# gesture_control_robot_rx.net
KiCad netlist of a schematic drawn in EAGLE
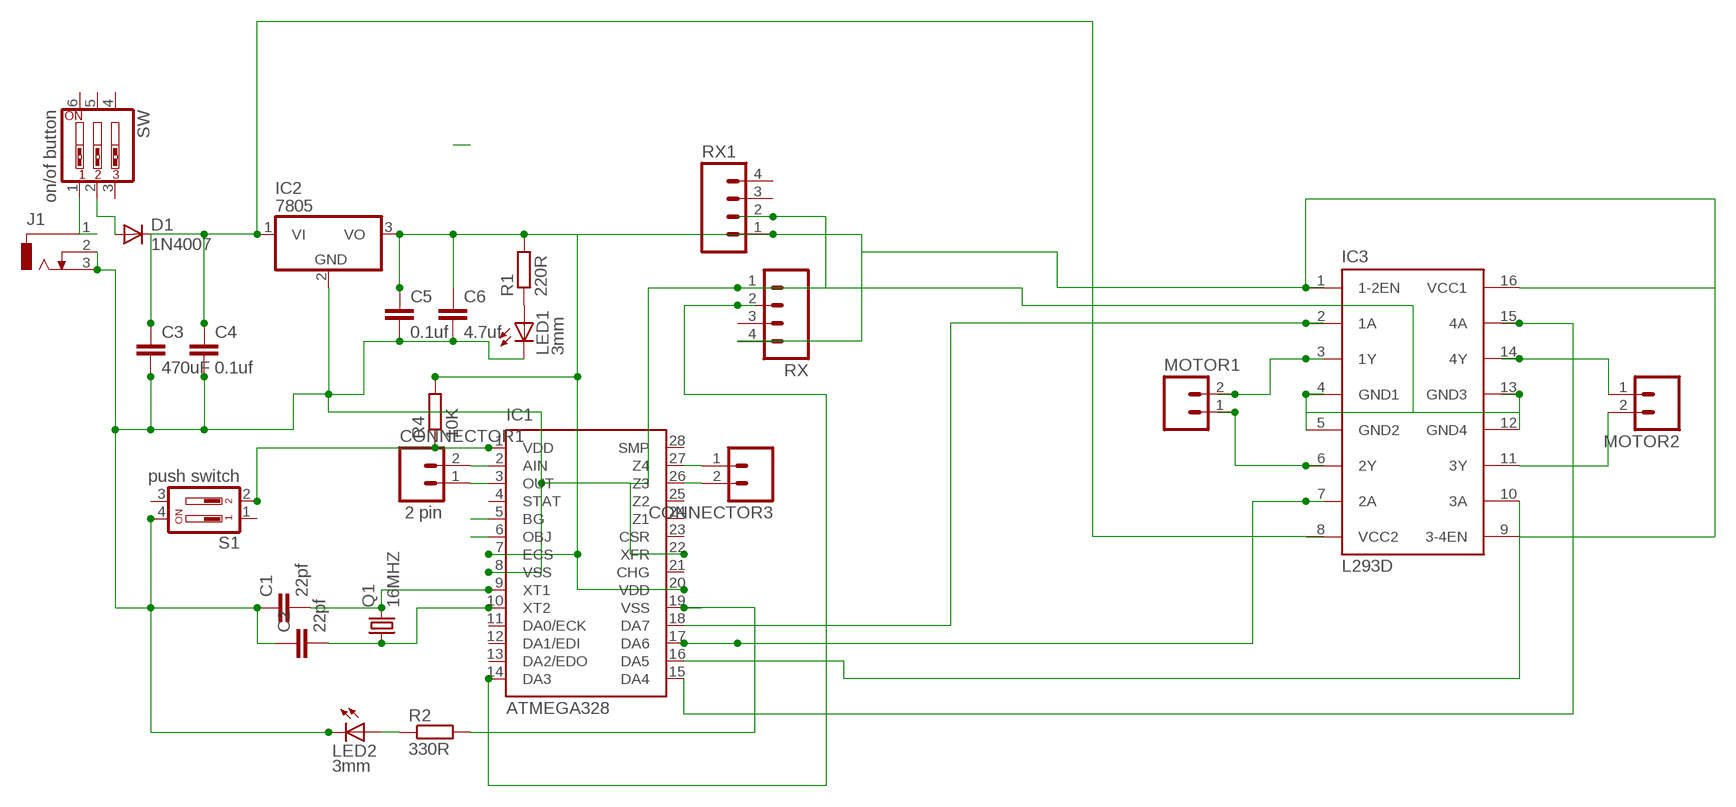
[diagram p0: schematic, sheet 1]

(export (version "E")
  (design (tool "Eeschema 10.0.6"))
  (components
    (comp (ref "C1")
      (value "22pf")
      (footprint "eagle-import:C2.5-2")
      (libsource (lib "eagle-import") (part "C2.5/2"))
    )
    (comp (ref "C2")
      (value "22pf")
      (footprint "eagle-import:C2.5-2")
      (libsource (lib "eagle-import") (part "C2.5/2"))
    )
    (comp (ref "C3")
      (value "470uF")
      (footprint "eagle-import:C2.5-2")
      (libsource (lib "eagle-import") (part "C2.5/2"))
    )
    (comp (ref "C4")
      (value "0.1uf")
      (footprint "eagle-import:C2.5-2")
      (libsource (lib "eagle-import") (part "C2.5/2"))
    )
    (comp (ref "C5")
      (value "0.1uf")
      (footprint "eagle-import:C2.5-2")
      (libsource (lib "eagle-import") (part "C2.5/2"))
    )
    (comp (ref "C6")
      (value "4.7uf")
      (footprint "eagle-import:C2.5-2")
      (libsource (lib "eagle-import") (part "C2.5/2"))
    )
    (comp (ref "CONNECTOR1")
      (value "2 pin")
      (footprint "eagle-import:02P")
      (fields (field (name "OC_FARNELL") "unknown") (field (name "OC_NEWARK") "unknown"))
      (libsource (lib "eagle-import") (part "M02"))
    )
    (comp (ref "CONNECTOR3")
      (value "M02")
      (footprint "eagle-import:02P")
      (fields (field (name "OC_FARNELL") "unknown") (field (name "OC_NEWARK") "unknown"))
      (libsource (lib "eagle-import") (part "M02"))
    )
    (comp (ref "D1")
      (value "1N4007")
      (footprint "eagle-import:DO41-10")
      (libsource (lib "eagle-import") (part "1N4004"))
    )
    (comp (ref "IC1")
      (value "ATMEGA328")
      (footprint "eagle-import:DIL28-3")
      (libsource (lib "eagle-import") (part "QT9701BD"))
    )
    (comp (ref "IC2")
      (value "7805")
      (footprint "eagle-import:TO220V")
      (libsource (lib "eagle-import") (part "78TV6"))
    )
    (comp (ref "IC3")
      (value "L293D")
      (footprint "eagle-import:DIL16")
      (libsource (lib "eagle-import") (part "L293D"))
    )
    (comp (ref "J1")
      (value "DCJ0303")
      (footprint "eagle-import:DCJ0303")
      (libsource (lib "eagle-import") (part "DCJ0303"))
    )
    (comp (ref "LED1")
      (value "3mm")
      (footprint "eagle-import:LED3MM")
      (libsource (lib "eagle-import") (part "LED3MM"))
    )
    (comp (ref "LED2")
      (value "3mm")
      (footprint "eagle-import:LED3MM")
      (libsource (lib "eagle-import") (part "LED3MM"))
    )
    (comp (ref "MOTOR1")
      (value "M02")
      (footprint "eagle-import:02P")
      (fields (field (name "OC_FARNELL") "unknown") (field (name "OC_NEWARK") "unknown"))
      (libsource (lib "eagle-import") (part "M02"))
    )
    (comp (ref "MOTOR2")
      (value "M02")
      (footprint "eagle-import:02P")
      (libsource (lib "eagle-import") (part "M02"))
    )
    (comp (ref "Q1")
      (value "16MHZ")
      (footprint "eagle-import:HC49_S")
      (libsource (lib "eagle-import") (part "CRYSTALHC49S"))
    )
    (comp (ref "R1")
      (value "220R")
      (footprint "eagle-import:0207_10")
      (libsource (lib "eagle-import") (part "R-EU_0207/10"))
    )
    (comp (ref "R2")
      (value "330R")
      (footprint "eagle-import:0207_10")
      (libsource (lib "eagle-import") (part "R-EU_0207/10"))
    )
    (comp (ref "R4")
      (value "10K")
      (footprint "eagle-import:0207_10")
      (libsource (lib "eagle-import") (part "R-EU_0207/10"))
    )
    (comp (ref "RX")
      (value "M04")
      (footprint "eagle-import:04P")
      (libsource (lib "eagle-import") (part "M04"))
    )
    (comp (ref "RX1")
      (value "M04")
      (footprint "eagle-import:04P")
      (fields (field (name "OC_FARNELL") "unknown") (field (name "OC_NEWARK") "unknown"))
      (libsource (lib "eagle-import") (part "M04"))
    )
    (comp (ref "S1")
      (value "push switch")
      (footprint "eagle-import:DP-02")
      (fields (field (name "MPN") "MCDP02"))
      (libsource (lib "eagle-import") (part "DP02"))
    )
    (comp (ref "SW")
      (value "on/of button")
      (footprint "eagle-import:EDG-03")
      (libsource (lib "eagle-import") (part "SW_DIP-3"))
    )
  )
  (nets
    (net (code "1") (name "Net-(D1-PadA)") (class "Default")
      (node (ref "D1") (pin "A") (pinfunction "A_A") (pintype "passive"))
      (node (ref "SW") (pin "2") (pinfunction "2_2") (pintype "passive"))
    )
    (net (code "2") (name "Net-(IC1-AIN)") (class "Default")
      (node (ref "CONNECTOR1") (pin "2") (pinfunction "2_2") (pintype "passive"))
      (node (ref "IC1") (pin "2") (pinfunction "AIN_2") (pintype "input"))
    )
    (net (code "3") (name "Net-(IC1-DA3)") (class "Default")
      (node (ref "IC1") (pin "14") (pinfunction "DA3_14") (pintype "output"))
      (node (ref "RX") (pin "2") (pinfunction "2_2") (pintype "passive"))
    )
    (net (code "4") (name "Net-(IC1-DA4)") (class "Default")
      (node (ref "IC1") (pin "15") (pinfunction "DA4_15") (pintype "output"))
      (node (ref "IC3") (pin "15") (pinfunction "4A_15") (pintype "input"))
    )
    (net (code "5") (name "Net-(IC1-DA5)") (class "Default")
      (node (ref "IC1") (pin "16") (pinfunction "DA5_16") (pintype "output"))
      (node (ref "IC3") (pin "10") (pinfunction "3A_10") (pintype "input"))
    )
    (net (code "6") (name "Net-(IC1-DA6)") (class "Default")
      (node (ref "IC1") (pin "17") (pinfunction "DA6_17") (pintype "output"))
      (node (ref "IC3") (pin "7") (pinfunction "2A_7") (pintype "input"))
    )
    (net (code "7") (name "Net-(IC1-DA7)") (class "Default")
      (node (ref "IC1") (pin "18") (pinfunction "DA7_18") (pintype "output"))
      (node (ref "IC3") (pin "2") (pinfunction "1A_2") (pintype "input"))
    )
    (net (code "8") (name "Net-(IC1-ECS)") (class "Default")
      (node (ref "C5") (pin "1") (pinfunction "1_1") (pintype "passive"))
      (node (ref "C6") (pin "1") (pinfunction "1_1") (pintype "passive"))
      (node (ref "IC1") (pin "20") (pinfunction "VDD_20") (pintype "input"))
      (node (ref "IC1") (pin "7") (pinfunction "ECS_7") (pintype "output"))
      (node (ref "IC2") (pin "3") (pinfunction "VO_3") (pintype "passive"))
      (node (ref "IC3") (pin "1") (pinfunction "1-2EN_1") (pintype "input"))
      (node (ref "IC3") (pin "16") (pinfunction "VCC1_16") (pintype "power_in"))
      (node (ref "IC3") (pin "9") (pinfunction "3-4EN_9") (pintype "input"))
      (node (ref "R1") (pin "2") (pinfunction "2_2") (pintype "passive"))
      (node (ref "R4") (pin "2") (pinfunction "2_2") (pintype "passive"))
      (node (ref "RX") (pin "4") (pinfunction "4_4") (pintype "passive"))
      (node (ref "RX1") (pin "1") (pinfunction "1_1") (pintype "passive"))
    )
    (net (code "9") (name "Net-(IC1-OUT)") (class "Default")
      (node (ref "CONNECTOR1") (pin "1") (pinfunction "1_1") (pintype "passive"))
      (node (ref "IC1") (pin "3") (pinfunction "OUT_3") (pintype "output"))
    )
    (net (code "10") (name "Net-(IC1-VDD-Pad1)") (class "Default")
      (node (ref "IC1") (pin "1") (pinfunction "VDD_1") (pintype "input"))
      (node (ref "R4") (pin "1") (pinfunction "1_1") (pintype "passive"))
      (node (ref "S1") (pin "2") (pinfunction "2_2") (pintype "passive"))
    )
    (net (code "11") (name "Net-(IC1-VSS-Pad19)") (class "Default")
      (node (ref "IC1") (pin "19") (pinfunction "VSS_19") (pintype "input"))
      (node (ref "R2") (pin "2") (pinfunction "2_2") (pintype "passive"))
    )
    (net (code "12") (name "Net-(IC1-XFR)") (class "Default")
      (node (ref "C1") (pin "1") (pinfunction "1_1") (pintype "passive"))
      (node (ref "C2") (pin "1") (pinfunction "1_1") (pintype "passive"))
      (node (ref "C3") (pin "2") (pinfunction "2_2") (pintype "passive"))
      (node (ref "C4") (pin "2") (pinfunction "2_2") (pintype "passive"))
      (node (ref "C5") (pin "2") (pinfunction "2_2") (pintype "passive"))
      (node (ref "C6") (pin "2") (pinfunction "2_2") (pintype "passive"))
      (node (ref "IC1") (pin "22") (pinfunction "XFR_22") (pintype "output"))
      (node (ref "IC1") (pin "8") (pinfunction "VSS_8") (pintype "input"))
      (node (ref "IC2") (pin "2") (pinfunction "GND_2") (pintype "passive"))
      (node (ref "IC3") (pin "12") (pinfunction "GND4_12") (pintype "power_in"))
      (node (ref "IC3") (pin "13") (pinfunction "GND3_13") (pintype "power_in"))
      (node (ref "IC3") (pin "4") (pinfunction "GND1_4") (pintype "power_in"))
      (node (ref "IC3") (pin "5") (pinfunction "GND2_5") (pintype "power_in"))
      (node (ref "J1") (pin "2") (pinfunction "2_2") (pintype "passive"))
      (node (ref "J1") (pin "3") (pinfunction "3_3") (pintype "passive"))
      (node (ref "LED1") (pin "K") (pinfunction "C_K") (pintype "passive"))
      (node (ref "LED2") (pin "K") (pinfunction "C_K") (pintype "passive"))
      (node (ref "RX") (pin "1") (pinfunction "1_1") (pintype "passive"))
      (node (ref "RX1") (pin "2") (pinfunction "2_2") (pintype "passive"))
      (node (ref "S1") (pin "4") (pinfunction "4_4") (pintype "passive"))
    )
    (net (code "13") (name "Net-(IC1-XT1)") (class "Default")
      (node (ref "C1") (pin "2") (pinfunction "2_2") (pintype "passive"))
      (node (ref "IC1") (pin "9") (pinfunction "XT1_9") (pintype "input"))
      (node (ref "Q1") (pin "2") (pinfunction "2_2") (pintype "passive"))
    )
    (net (code "14") (name "Net-(IC1-XT2)") (class "Default")
      (node (ref "C2") (pin "2") (pinfunction "2_2") (pintype "passive"))
      (node (ref "IC1") (pin "10") (pinfunction "XT2_10") (pintype "output"))
      (node (ref "Q1") (pin "1") (pinfunction "1_1") (pintype "passive"))
    )
    (net (code "15") (name "Net-(IC1-Z3)") (class "Default")
      (node (ref "CONNECTOR3") (pin "2") (pinfunction "2_2") (pintype "passive"))
      (node (ref "IC1") (pin "26") (pinfunction "Z3_26") (pintype "output"))
    )
    (net (code "16") (name "Net-(IC1-Z4)") (class "Default")
      (node (ref "CONNECTOR3") (pin "1") (pinfunction "1_1") (pintype "passive"))
      (node (ref "IC1") (pin "27") (pinfunction "Z4_27") (pintype "output"))
    )
    (net (code "17") (name "Net-(IC2-VI)") (class "Default")
      (node (ref "C3") (pin "1") (pinfunction "1_1") (pintype "passive"))
      (node (ref "C4") (pin "1") (pinfunction "1_1") (pintype "passive"))
      (node (ref "D1") (pin "C") (pinfunction "C_C") (pintype "passive"))
      (node (ref "IC2") (pin "1") (pinfunction "VI_1") (pintype "input"))
      (node (ref "IC3") (pin "8") (pinfunction "VCC2_8") (pintype "power_in"))
    )
    (net (code "18") (name "Net-(IC3-1Y)") (class "Default")
      (node (ref "IC3") (pin "3") (pinfunction "1Y_3") (pintype "output"))
      (node (ref "MOTOR1") (pin "2") (pinfunction "2_2") (pintype "passive"))
    )
    (net (code "19") (name "Net-(IC3-2Y)") (class "Default")
      (node (ref "IC3") (pin "6") (pinfunction "2Y_6") (pintype "output"))
      (node (ref "MOTOR1") (pin "1") (pinfunction "1_1") (pintype "passive"))
    )
    (net (code "20") (name "Net-(IC3-3Y)") (class "Default")
      (node (ref "IC3") (pin "11") (pinfunction "3Y_11") (pintype "output"))
      (node (ref "MOTOR2") (pin "2") (pinfunction "2_2") (pintype "passive"))
    )
    (net (code "21") (name "Net-(IC3-4Y)") (class "Default")
      (node (ref "IC3") (pin "14") (pinfunction "4Y_14") (pintype "output"))
      (node (ref "MOTOR2") (pin "1") (pinfunction "1_1") (pintype "passive"))
    )
    (net (code "22") (name "Net-(J1-Pad1)") (class "Default")
      (node (ref "J1") (pin "1") (pinfunction "1_1") (pintype "passive"))
      (node (ref "SW") (pin "1") (pinfunction "1_1") (pintype "passive"))
    )
    (net (code "23") (name "Net-(LED1-PadA)") (class "Default")
      (node (ref "LED1") (pin "A") (pinfunction "A_A") (pintype "passive"))
      (node (ref "R1") (pin "1") (pinfunction "1_1") (pintype "passive"))
    )
    (net (code "24") (name "Net-(LED2-PadA)") (class "Default")
      (node (ref "LED2") (pin "A") (pinfunction "A_A") (pintype "passive"))
      (node (ref "R2") (pin "1") (pinfunction "1_1") (pintype "passive"))
    )
    (net (code "25") (name "unconnected-(IC1-BG-Pad5)") (class "Default")
      (node (ref "IC1") (pin "5") (pinfunction "BG_5") (pintype "input"))
    )
    (net (code "26") (name "unconnected-(IC1-CHG-Pad21)") (class "Default")
      (node (ref "IC1") (pin "21") (pinfunction "CHG_21") (pintype "output"))
    )
    (net (code "27") (name "unconnected-(IC1-CSR-Pad23)") (class "Default")
      (node (ref "IC1") (pin "23") (pinfunction "CSR_23") (pintype "output"))
    )
    (net (code "28") (name "unconnected-(IC1-DA0{slash}ECK-Pad11)") (class "Default")
      (node (ref "IC1") (pin "11") (pinfunction "DA0/ECK_11") (pintype "output"))
    )
    (net (code "29") (name "unconnected-(IC1-DA1{slash}EDI-Pad12)") (class "Default")
      (node (ref "IC1") (pin "12") (pinfunction "DA1/EDI_12") (pintype "output"))
    )
    (net (code "30") (name "unconnected-(IC1-DA2{slash}EDO-Pad13)") (class "Default")
      (node (ref "IC1") (pin "13") (pinfunction "DA2/EDO_13") (pintype "output"))
    )
    (net (code "31") (name "unconnected-(IC1-OBJ-Pad6)") (class "Default")
      (node (ref "IC1") (pin "6") (pinfunction "OBJ_6") (pintype "input"))
    )
    (net (code "32") (name "unconnected-(IC1-SMP-Pad28)") (class "Default")
      (node (ref "IC1") (pin "28") (pinfunction "SMP_28") (pintype "output"))
    )
    (net (code "33") (name "unconnected-(IC1-STAT-Pad4)") (class "Default")
      (node (ref "IC1") (pin "4") (pinfunction "STAT_4") (pintype "output"))
    )
    (net (code "34") (name "unconnected-(IC1-Z1-Pad24)") (class "Default")
      (node (ref "IC1") (pin "24") (pinfunction "Z1_24") (pintype "output"))
    )
    (net (code "35") (name "unconnected-(IC1-Z2-Pad25)") (class "Default")
      (node (ref "IC1") (pin "25") (pinfunction "Z2_25") (pintype "output"))
    )
    (net (code "36") (name "unconnected-(RX-Pad3)") (class "Default")
      (node (ref "RX") (pin "3") (pinfunction "3_3") (pintype "passive"))
    )
    (net (code "37") (name "unconnected-(RX1-Pad3)") (class "Default")
      (node (ref "RX1") (pin "3") (pinfunction "3_3") (pintype "passive"))
    )
    (net (code "38") (name "unconnected-(RX1-Pad4)") (class "Default")
      (node (ref "RX1") (pin "4") (pinfunction "4_4") (pintype "passive"))
    )
    (net (code "39") (name "unconnected-(S1-Pad1)") (class "Default")
      (node (ref "S1") (pin "1") (pinfunction "1_1") (pintype "passive"))
    )
    (net (code "40") (name "unconnected-(S1-Pad3)") (class "Default")
      (node (ref "S1") (pin "3") (pinfunction "3_3") (pintype "passive"))
    )
    (net (code "41") (name "unconnected-(SW-Pad3)") (class "Default")
      (node (ref "SW") (pin "3") (pinfunction "3_3") (pintype "passive"))
    )
    (net (code "42") (name "unconnected-(SW-Pad4)") (class "Default")
      (node (ref "SW") (pin "4") (pinfunction "4_4") (pintype "passive"))
    )
    (net (code "43") (name "unconnected-(SW-Pad5)") (class "Default")
      (node (ref "SW") (pin "5") (pinfunction "5_5") (pintype "passive"))
    )
    (net (code "44") (name "unconnected-(SW-Pad6)") (class "Default")
      (node (ref "SW") (pin "6") (pinfunction "6_6") (pintype "passive"))
    )
  )
)
